# Optocouplers.net
KiCad netlist of a schematic drawn in Altium Designer
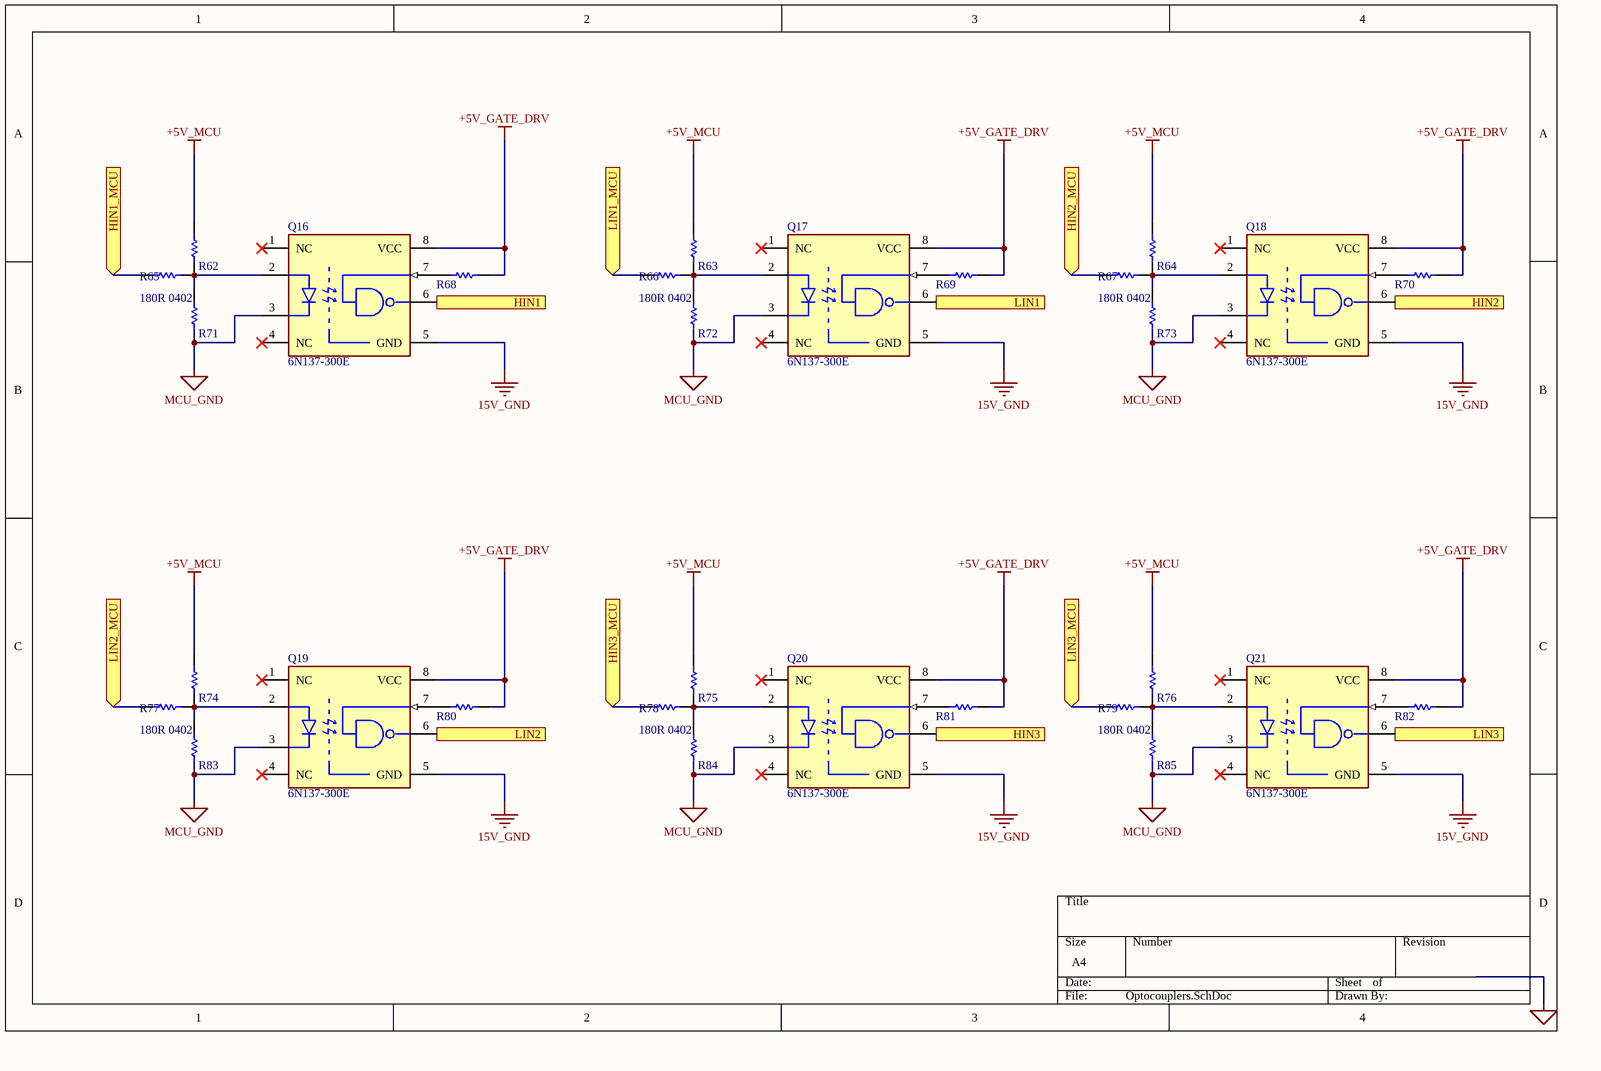
[diagram p0: Optocouplers.SchDoc]

(export (version "E")
  (design (tool "Eeschema 10.0.6"))
  (components
    (comp (ref "Q16")
      (value "6N137-300E")
      (footprint "FP-6N137-300E-MFG")
      (description "6N137 – High-Speed Optocoupler-SOP8")
      (fields
        (field (name "MANUFACTURER") "Broadcom")
        (field (name "OCTOPART") "https://octopart.com/6n137-300e-broadcom-71125550")
      )
      (libsource (lib "Altium Content Vault") (part "086db94909ba3b4bba0ec19532872cc"))
    )
    (comp (ref "Q17")
      (value "6N137-300E")
      (footprint "FP-6N137-300E-MFG")
      (description "6N137 – High-Speed Optocoupler-SOP8")
      (fields
        (field (name "MANUFACTURER") "Broadcom")
        (field (name "OCTOPART") "https://octopart.com/6n137-300e-broadcom-71125550")
      )
      (libsource (lib "Altium Content Vault") (part "086db94909ba3b4bba0ec19532872cc"))
    )
    (comp (ref "Q18")
      (value "6N137-300E")
      (footprint "FP-6N137-300E-MFG")
      (description "6N137 – High-Speed Optocoupler-SOP8")
      (fields
        (field (name "MANUFACTURER") "Broadcom")
        (field (name "OCTOPART") "https://octopart.com/6n137-300e-broadcom-71125550")
      )
      (libsource (lib "Altium Content Vault") (part "086db94909ba3b4bba0ec19532872cc"))
    )
    (comp (ref "Q19")
      (value "6N137-300E")
      (footprint "FP-6N137-300E-MFG")
      (description "6N137 – High-Speed Optocoupler-SOP8")
      (fields
        (field (name "MANUFACTURER") "Broadcom")
        (field (name "OCTOPART") "https://octopart.com/6n137-300e-broadcom-71125550")
      )
      (libsource (lib "Altium Content Vault") (part "086db94909ba3b4bba0ec19532872cc"))
    )
    (comp (ref "Q20")
      (value "6N137-300E")
      (footprint "FP-6N137-300E-MFG")
      (description "6N137 – High-Speed Optocoupler-SOP8")
      (fields
        (field (name "MANUFACTURER") "Broadcom")
        (field (name "OCTOPART") "https://octopart.com/6n137-300e-broadcom-71125550")
      )
      (libsource (lib "Altium Content Vault") (part "086db94909ba3b4bba0ec19532872cc"))
    )
    (comp (ref "Q21")
      (value "6N137-300E")
      (footprint "FP-6N137-300E-MFG")
      (description "6N137 – High-Speed Optocoupler-SOP8")
      (fields
        (field (name "MANUFACTURER") "Broadcom")
        (field (name "OCTOPART") "https://octopart.com/6n137-300e-broadcom-71125550")
      )
      (libsource (lib "Altium Content Vault") (part "086db94909ba3b4bba0ec19532872cc"))
    )
    (comp (ref "R62")
      (value "0R 0603")
      (footprint "R0603")
      (description "0 Ohm 1/10 Watt Resistor 1% Tolerance RC0603FR-070RL – 0603 Package")
      (libsource (lib "1kW_BLDC_Controller") (part "R0000 0603"))
    )
    (comp (ref "R63")
      (value "0R 0603")
      (footprint "R0603")
      (description "0 Ohm 1/10 Watt Resistor 1% Tolerance RC0603FR-070RL – 0603 Package")
      (libsource (lib "1kW_BLDC_Controller") (part "R0000 0603"))
    )
    (comp (ref "R64")
      (value "0R 0603")
      (footprint "R0603")
      (description "0 Ohm 1/10 Watt Resistor 1% Tolerance RC0603FR-070RL – 0603 Package")
      (libsource (lib "1kW_BLDC_Controller") (part "R0000 0603"))
    )
    (comp (ref "R65")
      (value "180R 0402")
      (footprint "R08050402")
      (description "180 Ohm 1/4 Watt Resistor – 0402 Package")
      (libsource (lib "1kW_BLDC_Controller") (part "R0805-0402"))
    )
    (comp (ref "R66")
      (value "180R 0402")
      (footprint "R08050402")
      (description "180 Ohm 1/4 Watt Resistor – 0402 Package")
      (libsource (lib "1kW_BLDC_Controller") (part "R0805-0402"))
    )
    (comp (ref "R67")
      (value "180R 0402")
      (footprint "R08050402")
      (description "180 Ohm 1/4 Watt Resistor – 0402 Package")
      (libsource (lib "1kW_BLDC_Controller") (part "R0805-0402"))
    )
    (comp (ref "R68")
      (value "0R 0603")
      (footprint "R0603")
      (description "0 Ohm 1/10 Watt Resistor 1% Tolerance RC0603FR-070RL – 0603 Package")
      (libsource (lib "1kW_BLDC_Controller") (part "R0000 0603"))
    )
    (comp (ref "R69")
      (value "0R 0603")
      (footprint "R0603")
      (description "0 Ohm 1/10 Watt Resistor 1% Tolerance RC0603FR-070RL – 0603 Package")
      (libsource (lib "1kW_BLDC_Controller") (part "R0000 0603"))
    )
    (comp (ref "R70")
      (value "0R 0603")
      (footprint "R0603")
      (description "0 Ohm 1/10 Watt Resistor 1% Tolerance RC0603FR-070RL – 0603 Package")
      (libsource (lib "1kW_BLDC_Controller") (part "R0000 0603"))
    )
    (comp (ref "R71")
      (value "0R 0603")
      (footprint "R0603")
      (description "0 Ohm 1/10 Watt Resistor 1% Tolerance RC0603FR-070RL – 0603 Package")
      (libsource (lib "1kW_BLDC_Controller") (part "R0000 0603"))
    )
    (comp (ref "R72")
      (value "0R 0603")
      (footprint "R0603")
      (description "0 Ohm 1/10 Watt Resistor 1% Tolerance RC0603FR-070RL – 0603 Package")
      (libsource (lib "1kW_BLDC_Controller") (part "R0000 0603"))
    )
    (comp (ref "R73")
      (value "0R 0603")
      (footprint "R0603")
      (description "0 Ohm 1/10 Watt Resistor 1% Tolerance RC0603FR-070RL – 0603 Package")
      (libsource (lib "1kW_BLDC_Controller") (part "R0000 0603"))
    )
    (comp (ref "R74")
      (value "0R 0603")
      (footprint "R0603")
      (description "0 Ohm 1/10 Watt Resistor 1% Tolerance RC0603FR-070RL – 0603 Package")
      (libsource (lib "1kW_BLDC_Controller") (part "R0000 0603"))
    )
    (comp (ref "R75")
      (value "0R 0603")
      (footprint "R0603")
      (description "0 Ohm 1/10 Watt Resistor 1% Tolerance RC0603FR-070RL – 0603 Package")
      (libsource (lib "1kW_BLDC_Controller") (part "R0000 0603"))
    )
    (comp (ref "R76")
      (value "0R 0603")
      (footprint "R0603")
      (description "0 Ohm 1/10 Watt Resistor 1% Tolerance RC0603FR-070RL – 0603 Package")
      (libsource (lib "1kW_BLDC_Controller") (part "R0000 0603"))
    )
    (comp (ref "R77")
      (value "180R 0402")
      (footprint "R08050402")
      (description "180 Ohm 1/4 Watt Resistor – 0402 Package")
      (libsource (lib "1kW_BLDC_Controller") (part "R0805-0402"))
    )
    (comp (ref "R78")
      (value "180R 0402")
      (footprint "R08050402")
      (description "180 Ohm 1/4 Watt Resistor – 0402 Package")
      (libsource (lib "1kW_BLDC_Controller") (part "R0805-0402"))
    )
    (comp (ref "R79")
      (value "180R 0402")
      (footprint "R08050402")
      (description "180 Ohm 1/4 Watt Resistor – 0402 Package")
      (libsource (lib "1kW_BLDC_Controller") (part "R0805-0402"))
    )
    (comp (ref "R80")
      (value "0R 0603")
      (footprint "R0603")
      (description "0 Ohm 1/10 Watt Resistor 1% Tolerance RC0603FR-070RL – 0603 Package")
      (libsource (lib "1kW_BLDC_Controller") (part "R0000 0603"))
    )
    (comp (ref "R81")
      (value "0R 0603")
      (footprint "R0603")
      (description "0 Ohm 1/10 Watt Resistor 1% Tolerance RC0603FR-070RL – 0603 Package")
      (libsource (lib "1kW_BLDC_Controller") (part "R0000 0603"))
    )
    (comp (ref "R82")
      (value "0R 0603")
      (footprint "R0603")
      (description "0 Ohm 1/10 Watt Resistor 1% Tolerance RC0603FR-070RL – 0603 Package")
      (libsource (lib "1kW_BLDC_Controller") (part "R0000 0603"))
    )
    (comp (ref "R83")
      (value "0R 0603")
      (footprint "R0603")
      (description "0 Ohm 1/10 Watt Resistor 1% Tolerance RC0603FR-070RL – 0603 Package")
      (libsource (lib "1kW_BLDC_Controller") (part "R0000 0603"))
    )
    (comp (ref "R84")
      (value "0R 0603")
      (footprint "R0603")
      (description "0 Ohm 1/10 Watt Resistor 1% Tolerance RC0603FR-070RL – 0603 Package")
      (libsource (lib "1kW_BLDC_Controller") (part "R0000 0603"))
    )
    (comp (ref "R85")
      (value "0R 0603")
      (footprint "R0603")
      (description "0 Ohm 1/10 Watt Resistor 1% Tolerance RC0603FR-070RL – 0603 Package")
      (libsource (lib "1kW_BLDC_Controller") (part "R0000 0603"))
    )
  )
  (nets
    (net (code "1") (name "+5V_GATE_DRV") (class "Default")
      (node (ref "Q16") (pin "8") (pinfunction "VCC_8") (pintype "power_in"))
      (node (ref "Q17") (pin "8") (pinfunction "VCC_8") (pintype "power_in"))
      (node (ref "Q18") (pin "8") (pinfunction "VCC_8") (pintype "power_in"))
      (node (ref "Q19") (pin "8") (pinfunction "VCC_8") (pintype "power_in"))
      (node (ref "Q20") (pin "8") (pinfunction "VCC_8") (pintype "power_in"))
      (node (ref "Q21") (pin "8") (pinfunction "VCC_8") (pintype "power_in"))
      (node (ref "R68") (pin "2") (pinfunction "2_2") (pintype "passive"))
      (node (ref "R69") (pin "2") (pinfunction "2_2") (pintype "passive"))
      (node (ref "R70") (pin "2") (pinfunction "2_2") (pintype "passive"))
      (node (ref "R80") (pin "2") (pinfunction "2_2") (pintype "passive"))
      (node (ref "R81") (pin "2") (pinfunction "2_2") (pintype "passive"))
      (node (ref "R82") (pin "2") (pinfunction "2_2") (pintype "passive"))
    )
    (net (code "2") (name "+5V_MCU") (class "Default")
      (node (ref "R62") (pin "2") (pinfunction "2_2") (pintype "passive"))
      (node (ref "R63") (pin "2") (pinfunction "2_2") (pintype "passive"))
      (node (ref "R64") (pin "2") (pinfunction "2_2") (pintype "passive"))
      (node (ref "R74") (pin "2") (pinfunction "2_2") (pintype "passive"))
      (node (ref "R75") (pin "2") (pinfunction "2_2") (pintype "passive"))
      (node (ref "R76") (pin "2") (pinfunction "2_2") (pintype "passive"))
    )
    (net (code "3") (name "/HIN1") (class "Default")
      (node (ref "Q16") (pin "6") (pinfunction "VO_6") (pintype "open_collector"))
    )
    (net (code "4") (name "/HIN1_MCU") (class "Default")
      (node (ref "R65") (pin "1") (pinfunction "1_1") (pintype "passive"))
    )
    (net (code "5") (name "/HIN2") (class "Default")
      (node (ref "Q18") (pin "6") (pinfunction "VO_6") (pintype "open_collector"))
    )
    (net (code "6") (name "/HIN2_MCU") (class "Default")
      (node (ref "R67") (pin "1") (pinfunction "1_1") (pintype "passive"))
    )
    (net (code "7") (name "/HIN3") (class "Default")
      (node (ref "Q20") (pin "6") (pinfunction "VO_6") (pintype "open_collector"))
    )
    (net (code "8") (name "/HIN3_MCU") (class "Default")
      (node (ref "R78") (pin "1") (pinfunction "1_1") (pintype "passive"))
    )
    (net (code "9") (name "/LIN1") (class "Default")
      (node (ref "Q17") (pin "6") (pinfunction "VO_6") (pintype "open_collector"))
    )
    (net (code "10") (name "/LIN1_MCU") (class "Default")
      (node (ref "R66") (pin "1") (pinfunction "1_1") (pintype "passive"))
    )
    (net (code "11") (name "/LIN2") (class "Default")
      (node (ref "Q19") (pin "6") (pinfunction "VO_6") (pintype "open_collector"))
    )
    (net (code "12") (name "/LIN2_MCU") (class "Default")
      (node (ref "R77") (pin "1") (pinfunction "1_1") (pintype "passive"))
    )
    (net (code "13") (name "/LIN3") (class "Default")
      (node (ref "Q21") (pin "6") (pinfunction "VO_6") (pintype "open_collector"))
    )
    (net (code "14") (name "/LIN3_MCU") (class "Default")
      (node (ref "R79") (pin "1") (pinfunction "1_1") (pintype "passive"))
    )
    (net (code "16") (name "15V_GND") (class "Default")
      (node (ref "Q16") (pin "5") (pinfunction "GND_5") (pintype "power_in"))
      (node (ref "Q17") (pin "5") (pinfunction "GND_5") (pintype "power_in"))
      (node (ref "Q18") (pin "5") (pinfunction "GND_5") (pintype "power_in"))
      (node (ref "Q19") (pin "5") (pinfunction "GND_5") (pintype "power_in"))
      (node (ref "Q20") (pin "5") (pinfunction "GND_5") (pintype "power_in"))
      (node (ref "Q21") (pin "5") (pinfunction "GND_5") (pintype "power_in"))
    )
    (net (code "17") (name "MCU_GND") (class "Default")
      (node (ref "Q16") (pin "3") (pinfunction "C_3") (pintype "passive"))
      (node (ref "Q17") (pin "3") (pinfunction "C_3") (pintype "passive"))
      (node (ref "Q18") (pin "3") (pinfunction "C_3") (pintype "passive"))
      (node (ref "Q19") (pin "3") (pinfunction "C_3") (pintype "passive"))
      (node (ref "Q20") (pin "3") (pinfunction "C_3") (pintype "passive"))
      (node (ref "Q21") (pin "3") (pinfunction "C_3") (pintype "passive"))
      (node (ref "R71") (pin "1") (pinfunction "1_1") (pintype "passive"))
      (node (ref "R72") (pin "1") (pinfunction "1_1") (pintype "passive"))
      (node (ref "R73") (pin "1") (pinfunction "1_1") (pintype "passive"))
      (node (ref "R83") (pin "1") (pinfunction "1_1") (pintype "passive"))
      (node (ref "R84") (pin "1") (pinfunction "1_1") (pintype "passive"))
      (node (ref "R85") (pin "1") (pinfunction "1_1") (pintype "passive"))
    )
    (net (code "18") (name "Net-(Q16-A)") (class "Default")
      (node (ref "Q16") (pin "2") (pinfunction "A_2") (pintype "passive"))
      (node (ref "R62") (pin "1") (pinfunction "1_1") (pintype "passive"))
      (node (ref "R65") (pin "2") (pinfunction "2_2") (pintype "passive"))
      (node (ref "R71") (pin "2") (pinfunction "2_2") (pintype "passive"))
    )
    (net (code "19") (name "Net-(Q16-VE)") (class "Default")
      (node (ref "Q16") (pin "7") (pinfunction "VE_7") (pintype "input"))
      (node (ref "R68") (pin "1") (pinfunction "1_1") (pintype "passive"))
    )
    (net (code "20") (name "Net-(Q17-A)") (class "Default")
      (node (ref "Q17") (pin "2") (pinfunction "A_2") (pintype "passive"))
      (node (ref "R63") (pin "1") (pinfunction "1_1") (pintype "passive"))
      (node (ref "R66") (pin "2") (pinfunction "2_2") (pintype "passive"))
      (node (ref "R72") (pin "2") (pinfunction "2_2") (pintype "passive"))
    )
    (net (code "21") (name "Net-(Q17-VE)") (class "Default")
      (node (ref "Q17") (pin "7") (pinfunction "VE_7") (pintype "input"))
      (node (ref "R69") (pin "1") (pinfunction "1_1") (pintype "passive"))
    )
    (net (code "22") (name "Net-(Q18-A)") (class "Default")
      (node (ref "Q18") (pin "2") (pinfunction "A_2") (pintype "passive"))
      (node (ref "R64") (pin "1") (pinfunction "1_1") (pintype "passive"))
      (node (ref "R67") (pin "2") (pinfunction "2_2") (pintype "passive"))
      (node (ref "R73") (pin "2") (pinfunction "2_2") (pintype "passive"))
    )
    (net (code "23") (name "Net-(Q18-VE)") (class "Default")
      (node (ref "Q18") (pin "7") (pinfunction "VE_7") (pintype "input"))
      (node (ref "R70") (pin "1") (pinfunction "1_1") (pintype "passive"))
    )
    (net (code "24") (name "Net-(Q19-A)") (class "Default")
      (node (ref "Q19") (pin "2") (pinfunction "A_2") (pintype "passive"))
      (node (ref "R74") (pin "1") (pinfunction "1_1") (pintype "passive"))
      (node (ref "R77") (pin "2") (pinfunction "2_2") (pintype "passive"))
      (node (ref "R83") (pin "2") (pinfunction "2_2") (pintype "passive"))
    )
    (net (code "25") (name "Net-(Q19-VE)") (class "Default")
      (node (ref "Q19") (pin "7") (pinfunction "VE_7") (pintype "input"))
      (node (ref "R80") (pin "1") (pinfunction "1_1") (pintype "passive"))
    )
    (net (code "26") (name "Net-(Q20-A)") (class "Default")
      (node (ref "Q20") (pin "2") (pinfunction "A_2") (pintype "passive"))
      (node (ref "R75") (pin "1") (pinfunction "1_1") (pintype "passive"))
      (node (ref "R78") (pin "2") (pinfunction "2_2") (pintype "passive"))
      (node (ref "R84") (pin "2") (pinfunction "2_2") (pintype "passive"))
    )
    (net (code "27") (name "Net-(Q20-VE)") (class "Default")
      (node (ref "Q20") (pin "7") (pinfunction "VE_7") (pintype "input"))
      (node (ref "R81") (pin "1") (pinfunction "1_1") (pintype "passive"))
    )
    (net (code "28") (name "Net-(Q21-A)") (class "Default")
      (node (ref "Q21") (pin "2") (pinfunction "A_2") (pintype "passive"))
      (node (ref "R76") (pin "1") (pinfunction "1_1") (pintype "passive"))
      (node (ref "R79") (pin "2") (pinfunction "2_2") (pintype "passive"))
      (node (ref "R85") (pin "2") (pinfunction "2_2") (pintype "passive"))
    )
    (net (code "29") (name "Net-(Q21-VE)") (class "Default")
      (node (ref "Q21") (pin "7") (pinfunction "VE_7") (pintype "input"))
      (node (ref "R82") (pin "1") (pinfunction "1_1") (pintype "passive"))
    )
    (net (code "30") (name "unconnected-(Q16-NC-Pad1)") (class "Default")
      (node (ref "Q16") (pin "1") (pinfunction "NC_1") (pintype "passive+no_connect"))
    )
    (net (code "31") (name "unconnected-(Q16-NC-Pad4)") (class "Default")
      (node (ref "Q16") (pin "4") (pinfunction "NC_4") (pintype "passive+no_connect"))
    )
    (net (code "32") (name "unconnected-(Q17-NC-Pad1)") (class "Default")
      (node (ref "Q17") (pin "1") (pinfunction "NC_1") (pintype "passive+no_connect"))
    )
    (net (code "33") (name "unconnected-(Q17-NC-Pad4)") (class "Default")
      (node (ref "Q17") (pin "4") (pinfunction "NC_4") (pintype "passive+no_connect"))
    )
    (net (code "34") (name "unconnected-(Q18-NC-Pad1)") (class "Default")
      (node (ref "Q18") (pin "1") (pinfunction "NC_1") (pintype "passive+no_connect"))
    )
    (net (code "35") (name "unconnected-(Q18-NC-Pad4)") (class "Default")
      (node (ref "Q18") (pin "4") (pinfunction "NC_4") (pintype "passive+no_connect"))
    )
    (net (code "36") (name "unconnected-(Q19-NC-Pad1)") (class "Default")
      (node (ref "Q19") (pin "1") (pinfunction "NC_1") (pintype "passive+no_connect"))
    )
    (net (code "37") (name "unconnected-(Q19-NC-Pad4)") (class "Default")
      (node (ref "Q19") (pin "4") (pinfunction "NC_4") (pintype "passive+no_connect"))
    )
    (net (code "38") (name "unconnected-(Q20-NC-Pad1)") (class "Default")
      (node (ref "Q20") (pin "1") (pinfunction "NC_1") (pintype "passive+no_connect"))
    )
    (net (code "39") (name "unconnected-(Q20-NC-Pad4)") (class "Default")
      (node (ref "Q20") (pin "4") (pinfunction "NC_4") (pintype "passive+no_connect"))
    )
    (net (code "40") (name "unconnected-(Q21-NC-Pad1)") (class "Default")
      (node (ref "Q21") (pin "1") (pinfunction "NC_1") (pintype "passive+no_connect"))
    )
    (net (code "41") (name "unconnected-(Q21-NC-Pad4)") (class "Default")
      (node (ref "Q21") (pin "4") (pinfunction "NC_4") (pintype "passive+no_connect"))
    )
  )
)
